# logic_vB.net
KiCad netlist of a schematic drawn in EAGLE
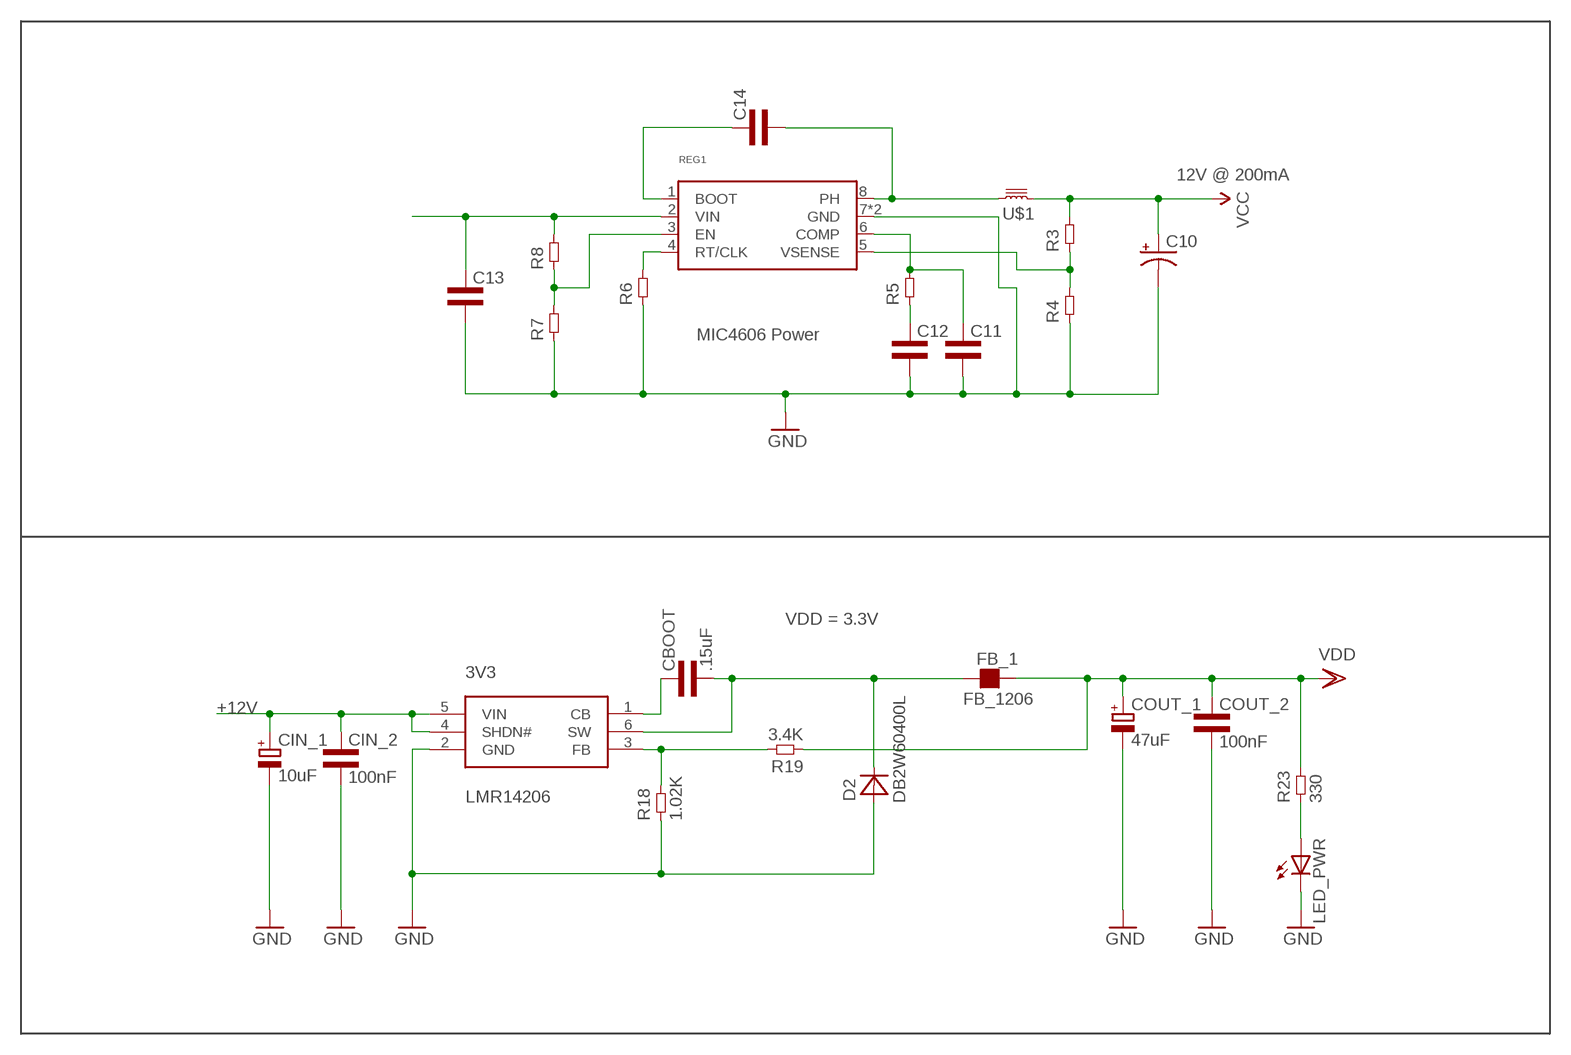
[diagram p0: schematic, sheet 1]
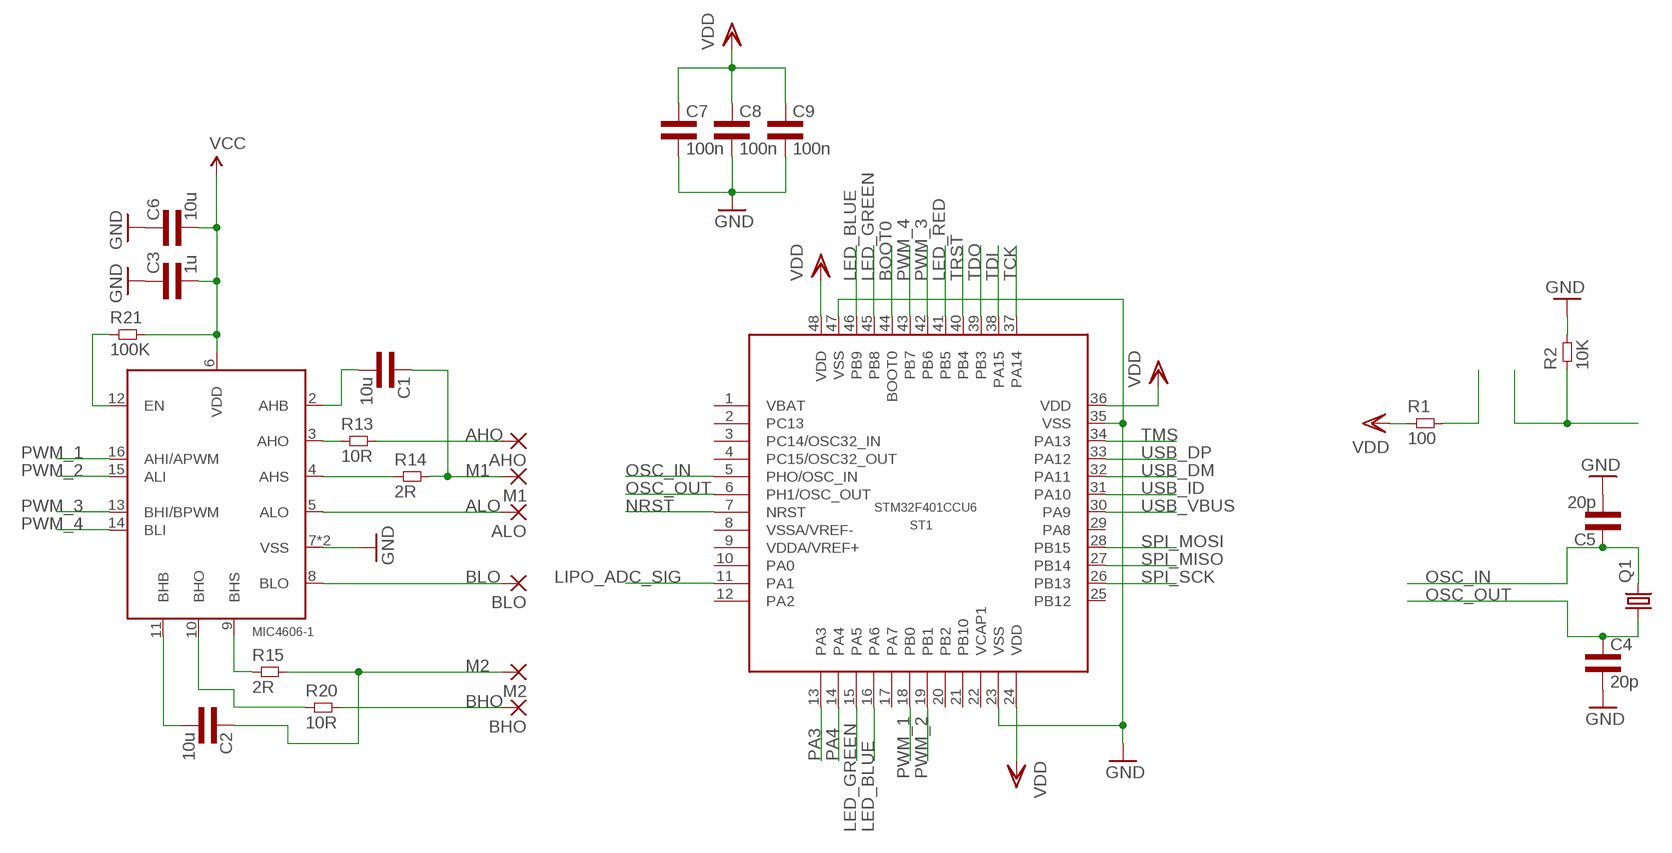
[diagram p1: schematic, sheet 2]
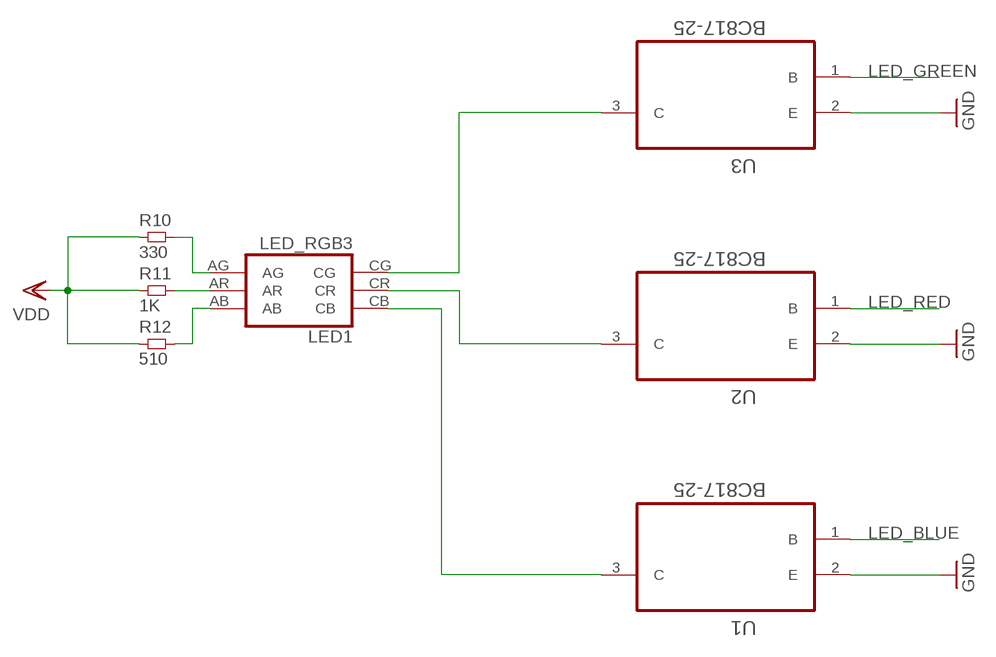
[diagram p2: schematic, sheet 3]
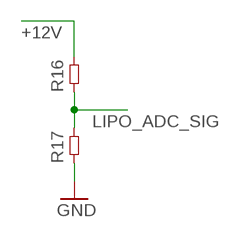
[diagram p3: schematic, sheet 4]

(export (version "E")
  (design (tool "Eeschema 10.0.6"))
  (components
    (comp (ref "R16")
      (value "RES0805L3")
      (footprint "eagle-import:0805L3")
      (libsource (lib "eagle-import") (part "RES0805L3"))
    )
    (comp (ref "R17")
      (value "RES0805L3")
      (footprint "eagle-import:0805L3")
      (libsource (lib "eagle-import") (part "RES0805L3"))
    )
    (comp (ref "AHO")
      (value "2,54/1,1")
      (footprint "eagle-import:2,54_1,1")
      (libsource (lib "eagle-import") (part "2,54/1,1"))
    )
    (comp (ref "ALO")
      (value "2,54/1,1")
      (footprint "eagle-import:2,54_1,1")
      (libsource (lib "eagle-import") (part "2,54/1,1"))
    )
    (comp (ref "BHO")
      (value "2,54/1,1")
      (footprint "eagle-import:2,54_1,1")
      (libsource (lib "eagle-import") (part "2,54/1,1"))
    )
    (comp (ref "BLO")
      (value "2,54/1,1")
      (footprint "eagle-import:2,54_1,1")
      (libsource (lib "eagle-import") (part "2,54/1,1"))
    )
    (comp (ref "C1")
      (value "10u")
      (footprint "eagle-import:0805L3")
      (libsource (lib "eagle-import") (part "CAP0805L3"))
    )
    (comp (ref "C2")
      (value "10u")
      (footprint "eagle-import:0805L3")
      (libsource (lib "eagle-import") (part "CAP0805L3"))
    )
    (comp (ref "C3")
      (value "1u")
      (footprint "eagle-import:0603L3")
      (libsource (lib "eagle-import") (part "CAP0603L3"))
    )
    (comp (ref "C4")
      (value "20p")
      (footprint "eagle-import:0402L3")
      (libsource (lib "eagle-import") (part "CAP0402L3"))
    )
    (comp (ref "C5")
      (value "20p")
      (footprint "eagle-import:0402L3")
      (libsource (lib "eagle-import") (part "CAP0402L3"))
    )
    (comp (ref "C6")
      (value "10u")
      (footprint "eagle-import:0603L3")
      (libsource (lib "eagle-import") (part "CAP0603L3"))
    )
    (comp (ref "C7")
      (value "100n")
      (footprint "eagle-import:0402L3")
      (libsource (lib "eagle-import") (part "CAP0402L3"))
    )
    (comp (ref "C8")
      (value "100n")
      (footprint "eagle-import:0402L3")
      (libsource (lib "eagle-import") (part "CAP0402L3"))
    )
    (comp (ref "C9")
      (value "100n")
      (footprint "eagle-import:0402L3")
      (libsource (lib "eagle-import") (part "CAP0402L3"))
    )
    (comp (ref "M1")
      (value "2,54/1,1")
      (footprint "eagle-import:2,54_1,1")
      (libsource (lib "eagle-import") (part "2,54/1,1"))
    )
    (comp (ref "M2")
      (value "2,54/1,1")
      (footprint "eagle-import:2,54_1,1")
      (libsource (lib "eagle-import") (part "2,54/1,1"))
    )
    (comp (ref "MD1")
      (value "MIC4606-1")
      (footprint "eagle-import:QFN44-16LD-PL-2")
      (libsource (lib "eagle-import") (part "MIC4606-1"))
    )
    (comp (ref "Q1")
      (value "CRYSTALCTS406")
      (footprint "eagle-import:CTS406")
      (libsource (lib "eagle-import") (part "CRYSTALCTS406"))
    )
    (comp (ref "R1")
      (value "100")
      (footprint "eagle-import:0402L3")
      (libsource (lib "eagle-import") (part "RES0402L3"))
    )
    (comp (ref "R2")
      (value "10K")
      (footprint "eagle-import:0402L3")
      (libsource (lib "eagle-import") (part "RES0402L3"))
    )
    (comp (ref "R13")
      (value "10R")
      (footprint "eagle-import:0805L3")
      (libsource (lib "eagle-import") (part "RES0805L3"))
    )
    (comp (ref "R14")
      (value "2R")
      (footprint "eagle-import:0805L3")
      (libsource (lib "eagle-import") (part "RES0805L3"))
    )
    (comp (ref "R15")
      (value "2R")
      (footprint "eagle-import:0805L3")
      (libsource (lib "eagle-import") (part "RES0805L3"))
    )
    (comp (ref "R20")
      (value "10R")
      (footprint "eagle-import:0805L3")
      (libsource (lib "eagle-import") (part "RES0805L3"))
    )
    (comp (ref "R21")
      (value "100K")
      (footprint "eagle-import:0603L3")
      (libsource (lib "eagle-import") (part "RES0603L3"))
    )
    (comp (ref "ST1")
      (value "STM32F401CCU6")
      (footprint "eagle-import:UFQFPN48")
      (libsource (lib "eagle-import") (part "STM32F401CCU6"))
    )
    (comp (ref "3V3")
      (value "LMR14206")
      (footprint "eagle-import:R-PDSO-G6")
      (libsource (lib "eagle-import") (part "LMR14206"))
    )
    (comp (ref "C10")
      (value "CPOL-US153CLV-0605")
      (footprint "eagle-import:153CLV-0605")
      (libsource (lib "eagle-import") (part "CPOL-US153CLV-0605"))
    )
    (comp (ref "C11")
      (value "CAP0603L3")
      (footprint "eagle-import:0603L3")
      (libsource (lib "eagle-import") (part "CAP0603L3"))
    )
    (comp (ref "C12")
      (value "CAP0603L3")
      (footprint "eagle-import:0603L3")
      (libsource (lib "eagle-import") (part "CAP0603L3"))
    )
    (comp (ref "C13")
      (value "CAP0805L3")
      (footprint "eagle-import:0805L3")
      (libsource (lib "eagle-import") (part "CAP0805L3"))
    )
    (comp (ref "C14")
      (value "CAP0603L3")
      (footprint "eagle-import:0603L3")
      (libsource (lib "eagle-import") (part "CAP0603L3"))
    )
    (comp (ref "CBOOT")
      (value ".15uF")
      (footprint "eagle-import:0603L3")
      (libsource (lib "eagle-import") (part "CAP0603L3"))
    )
    (comp (ref "CIN_1")
      (value "10uF")
      (footprint "eagle-import:B_3528-21W")
      (libsource (lib "eagle-import") (part "CPOL-EUB/3528-21W"))
    )
    (comp (ref "CIN_2")
      (value "100nF")
      (footprint "eagle-import:0603L3")
      (libsource (lib "eagle-import") (part "CAP0603L3"))
    )
    (comp (ref "COUT_1")
      (value "47uF")
      (footprint "eagle-import:B_3528-21W")
      (libsource (lib "eagle-import") (part "CPOL-EUB/3528-21W"))
    )
    (comp (ref "COUT_2")
      (value "100nF")
      (footprint "eagle-import:0603L3")
      (libsource (lib "eagle-import") (part "CAP0603L3"))
    )
    (comp (ref "D2")
      (value "DB2W60400L")
      (footprint "eagle-import:SC-109B")
      (libsource (lib "eagle-import") (part "DB2W60400L"))
    )
    (comp (ref "FB_1")
      (value "FB_1206")
      (footprint "eagle-import:L1206")
      (libsource (lib "eagle-import") (part "FB_1206"))
    )
    (comp (ref "LED_PWR")
      (value "LEDCHIP-LED0603")
      (footprint "eagle-import:CHIP-LED0603")
      (libsource (lib "eagle-import") (part "LEDCHIP-LED0603"))
    )
    (comp (ref "R3")
      (value "RES0603L3")
      (footprint "eagle-import:0603L3")
      (libsource (lib "eagle-import") (part "RES0603L3"))
    )
    (comp (ref "R4")
      (value "RES0603L3")
      (footprint "eagle-import:0603L3")
      (libsource (lib "eagle-import") (part "RES0603L3"))
    )
    (comp (ref "R5")
      (value "RES0603L3")
      (footprint "eagle-import:0603L3")
      (libsource (lib "eagle-import") (part "RES0603L3"))
    )
    (comp (ref "R6")
      (value "RES0603L3")
      (footprint "eagle-import:0603L3")
      (libsource (lib "eagle-import") (part "RES0603L3"))
    )
    (comp (ref "R7")
      (value "RES0603L3")
      (footprint "eagle-import:0603L3")
      (libsource (lib "eagle-import") (part "RES0603L3"))
    )
    (comp (ref "R8")
      (value "RES0603L3")
      (footprint "eagle-import:0603L3")
      (libsource (lib "eagle-import") (part "RES0603L3"))
    )
    (comp (ref "R18")
      (value "1.02K")
      (footprint "eagle-import:0402L3")
      (libsource (lib "eagle-import") (part "RES0402L3"))
    )
    (comp (ref "R19")
      (value "3.4K")
      (footprint "eagle-import:0402L3")
      (libsource (lib "eagle-import") (part "RES0402L3"))
    )
    (comp (ref "R23")
      (value "330")
      (footprint "eagle-import:0402L3")
      (libsource (lib "eagle-import") (part "RES0402L3"))
    )
    (comp (ref "REG1")
      (value "TPS54061")
      (footprint "eagle-import:S-PVSON-N8")
      (libsource (lib "eagle-import") (part "TPS54061"))
    )
    (comp (ref "U$1")
      (value "SDR0604")
      (footprint "eagle-import:SDR0604")
      (libsource (lib "eagle-import") (part "SDR0604"))
    )
    (comp (ref "LED1")
      (value "LED_RGB3")
      (footprint "eagle-import:RGBLED")
      (libsource (lib "eagle-import") (part "LED_RGB3"))
    )
    (comp (ref "R10")
      (value "330")
      (footprint "eagle-import:0402L3")
      (libsource (lib "eagle-import") (part "RES0402L3"))
    )
    (comp (ref "R11")
      (value "1K")
      (footprint "eagle-import:0402L3")
      (libsource (lib "eagle-import") (part "RES0402L3"))
    )
    (comp (ref "R12")
      (value "510")
      (footprint "eagle-import:0402L3")
      (libsource (lib "eagle-import") (part "RES0402L3"))
    )
    (comp (ref "U1")
      (value "BC817-25")
      (footprint "eagle-import:SOT95P240X97-3N")
      (libsource (lib "eagle-import") (part "BC817-25"))
    )
    (comp (ref "U2")
      (value "BC817-25")
      (footprint "eagle-import:SOT95P240X97-3N")
      (libsource (lib "eagle-import") (part "BC817-25"))
    )
    (comp (ref "U3")
      (value "BC817-25")
      (footprint "eagle-import:SOT95P240X97-3N")
      (libsource (lib "eagle-import") (part "BC817-25"))
    )
  )
  (nets
    (net (code "1") (name "+12V") (class "Default")
      (node (ref "3V3") (pin "4") (pinfunction "SHDN#_4") (pintype "bidirectional"))
      (node (ref "3V3") (pin "5") (pinfunction "VIN_5") (pintype "bidirectional"))
      (node (ref "C13") (pin "1") (pinfunction "1_1") (pintype "bidirectional"))
      (node (ref "CIN_1") (pin "+") (pinfunction "+_+") (pintype "passive"))
      (node (ref "CIN_2") (pin "P$1") (pinfunction "1_P$1") (pintype "bidirectional"))
      (node (ref "R16") (pin "2") (pinfunction "2_2") (pintype "bidirectional"))
      (node (ref "R8") (pin "P$2") (pinfunction "2_P$2") (pintype "bidirectional"))
      (node (ref "REG1") (pin "2") (pinfunction "VIN_2") (pintype "bidirectional"))
    )
    (net (code "2") (name "AHO") (class "Default")
      (node (ref "AHO") (pin "1") (pinfunction "P_1") (pintype "passive"))
      (node (ref "R13") (pin "2") (pinfunction "2_2") (pintype "bidirectional"))
    )
    (net (code "3") (name "ALO") (class "Default")
      (node (ref "ALO") (pin "1") (pinfunction "P_1") (pintype "passive"))
      (node (ref "MD1") (pin "5") (pinfunction "ALO_5") (pintype "bidirectional"))
    )
    (net (code "4") (name "BHO") (class "Default")
      (node (ref "BHO") (pin "1") (pinfunction "P_1") (pintype "passive"))
      (node (ref "R20") (pin "2") (pinfunction "2_2") (pintype "bidirectional"))
    )
    (net (code "5") (name "BLO") (class "Default")
      (node (ref "BLO") (pin "1") (pinfunction "P_1") (pintype "passive"))
      (node (ref "MD1") (pin "8") (pinfunction "BLO_8") (pintype "bidirectional"))
    )
    (net (code "6") (name "BOOT0") (class "Default")
      (node (ref "ST1") (pin "44") (pinfunction "BOOT0_44") (pintype "bidirectional"))
    )
    (net (code "7") (name "GND") (class "Default")
      (node (ref "3V3") (pin "2") (pinfunction "GND_2") (pintype "bidirectional"))
      (node (ref "C10") (pin "-") (pinfunction "-_-") (pintype "passive"))
      (node (ref "C11") (pin "P$2") (pinfunction "2_P$2") (pintype "bidirectional"))
      (node (ref "C12") (pin "P$2") (pinfunction "2_P$2") (pintype "bidirectional"))
      (node (ref "C13") (pin "2") (pinfunction "2_2") (pintype "bidirectional"))
      (node (ref "C3") (pin "P$1") (pinfunction "1_P$1") (pintype "bidirectional"))
      (node (ref "C4") (pin "P$2") (pinfunction "2_P$2") (pintype "bidirectional"))
      (node (ref "C5") (pin "P$2") (pinfunction "2_P$2") (pintype "bidirectional"))
      (node (ref "C6") (pin "P$1") (pinfunction "1_P$1") (pintype "bidirectional"))
      (node (ref "C7") (pin "P$2") (pinfunction "2_P$2") (pintype "bidirectional"))
      (node (ref "C8") (pin "P$2") (pinfunction "2_P$2") (pintype "bidirectional"))
      (node (ref "C9") (pin "P$2") (pinfunction "2_P$2") (pintype "bidirectional"))
      (node (ref "CIN_1") (pin "-") (pinfunction "-_-") (pintype "passive"))
      (node (ref "CIN_2") (pin "P$2") (pinfunction "2_P$2") (pintype "bidirectional"))
      (node (ref "COUT_1") (pin "-") (pinfunction "-_-") (pintype "passive"))
      (node (ref "COUT_2") (pin "P$2") (pinfunction "2_P$2") (pintype "bidirectional"))
      (node (ref "D2") (pin "2") (pinfunction "A_2") (pintype "passive"))
      (node (ref "LED_PWR") (pin "C") (pinfunction "C_C") (pintype "passive"))
      (node (ref "MD1") (pin "7") (pinfunction "VSS_7") (pintype "bidirectional"))
      (node (ref "MD1") (pin "TP") (pinfunction "VSS_TP") (pintype "bidirectional"))
      (node (ref "R17") (pin "1") (pinfunction "1_1") (pintype "bidirectional"))
      (node (ref "R18") (pin "P$1") (pinfunction "1_P$1") (pintype "bidirectional"))
      (node (ref "R2") (pin "P$2") (pinfunction "2_P$2") (pintype "bidirectional"))
      (node (ref "R4") (pin "P$1") (pinfunction "1_P$1") (pintype "bidirectional"))
      (node (ref "R6") (pin "P$1") (pinfunction "1_P$1") (pintype "bidirectional"))
      (node (ref "R7") (pin "P$1") (pinfunction "1_P$1") (pintype "bidirectional"))
      (node (ref "REG1") (pin "7") (pinfunction "GND_7") (pintype "bidirectional"))
      (node (ref "REG1") (pin "P$1") (pinfunction "GND_P$1") (pintype "bidirectional"))
      (node (ref "ST1") (pin "23") (pinfunction "VSS_23") (pintype "bidirectional"))
      (node (ref "ST1") (pin "35") (pinfunction "VSS_35") (pintype "bidirectional"))
      (node (ref "ST1") (pin "47") (pinfunction "VSS_47") (pintype "bidirectional"))
      (node (ref "U1") (pin "2") (pinfunction "E_2") (pintype "passive"))
      (node (ref "U2") (pin "2") (pinfunction "E_2") (pintype "passive"))
      (node (ref "U3") (pin "2") (pinfunction "E_2") (pintype "passive"))
    )
    (net (code "8") (name "LED_BLUE") (class "Default")
      (node (ref "ST1") (pin "16") (pinfunction "PA6_16") (pintype "bidirectional"))
      (node (ref "ST1") (pin "46") (pinfunction "PB9_46") (pintype "bidirectional"))
      (node (ref "U1") (pin "1") (pinfunction "B_1") (pintype "passive"))
    )
    (net (code "9") (name "LED_GREEN") (class "Default")
      (node (ref "ST1") (pin "15") (pinfunction "PA5_15") (pintype "bidirectional"))
      (node (ref "ST1") (pin "45") (pinfunction "PB8_45") (pintype "bidirectional"))
      (node (ref "U3") (pin "1") (pinfunction "B_1") (pintype "passive"))
    )
    (net (code "10") (name "LED_RED") (class "Default")
      (node (ref "ST1") (pin "41") (pinfunction "PB5_41") (pintype "bidirectional"))
      (node (ref "U2") (pin "1") (pinfunction "B_1") (pintype "passive"))
    )
    (net (code "11") (name "LIPO_ADC_SIG") (class "Default")
      (node (ref "R16") (pin "1") (pinfunction "1_1") (pintype "bidirectional"))
      (node (ref "R17") (pin "2") (pinfunction "2_2") (pintype "bidirectional"))
      (node (ref "ST1") (pin "11") (pinfunction "PA1_11") (pintype "bidirectional"))
    )
    (net (code "12") (name "M1") (class "Default")
      (node (ref "C1") (pin "1") (pinfunction "1_1") (pintype "bidirectional"))
      (node (ref "M1") (pin "1") (pinfunction "P_1") (pintype "passive"))
      (node (ref "R14") (pin "2") (pinfunction "2_2") (pintype "bidirectional"))
    )
    (net (code "13") (name "M2") (class "Default")
      (node (ref "C2") (pin "1") (pinfunction "1_1") (pintype "bidirectional"))
      (node (ref "M2") (pin "1") (pinfunction "P_1") (pintype "passive"))
      (node (ref "R15") (pin "2") (pinfunction "2_2") (pintype "bidirectional"))
    )
    (net (code "14") (name "NRST") (class "Default")
      (node (ref "ST1") (pin "7") (pinfunction "NRST_7") (pintype "bidirectional"))
    )
    (net (code "15") (name "Net-(3V3-CB)") (class "Default")
      (node (ref "3V3") (pin "1") (pinfunction "CB_1") (pintype "bidirectional"))
      (node (ref "CBOOT") (pin "P$1") (pinfunction "1_P$1") (pintype "bidirectional"))
    )
    (net (code "16") (name "Net-(3V3-FB)") (class "Default")
      (node (ref "3V3") (pin "3") (pinfunction "FB_3") (pintype "bidirectional"))
      (node (ref "R18") (pin "P$2") (pinfunction "2_P$2") (pintype "bidirectional"))
      (node (ref "R19") (pin "P$2") (pinfunction "2_P$2") (pintype "bidirectional"))
    )
    (net (code "17") (name "Net-(3V3-SW)") (class "Default")
      (node (ref "3V3") (pin "6") (pinfunction "SW_6") (pintype "bidirectional"))
      (node (ref "CBOOT") (pin "P$2") (pinfunction "2_P$2") (pintype "bidirectional"))
      (node (ref "D2") (pin "1") (pinfunction "C_1") (pintype "passive"))
      (node (ref "FB_1") (pin "1") (pinfunction "1_1") (pintype "passive"))
    )
    (net (code "18") (name "Net-(C11-1)") (class "Default")
      (node (ref "C11") (pin "P$1") (pinfunction "1_P$1") (pintype "bidirectional"))
      (node (ref "R5") (pin "P$2") (pinfunction "2_P$2") (pintype "bidirectional"))
      (node (ref "REG1") (pin "6") (pinfunction "COMP_6") (pintype "bidirectional"))
    )
    (net (code "19") (name "Net-(C12-1)") (class "Default")
      (node (ref "C12") (pin "P$1") (pinfunction "1_P$1") (pintype "bidirectional"))
      (node (ref "R5") (pin "P$1") (pinfunction "1_P$1") (pintype "bidirectional"))
    )
    (net (code "20") (name "Net-(C14-1)") (class "Default")
      (node (ref "C14") (pin "P$1") (pinfunction "1_P$1") (pintype "bidirectional"))
      (node (ref "REG1") (pin "1") (pinfunction "BOOT_1") (pintype "bidirectional"))
    )
    (net (code "21") (name "Net-(C14-2)") (class "Default")
      (node (ref "C14") (pin "P$2") (pinfunction "2_P$2") (pintype "bidirectional"))
      (node (ref "REG1") (pin "8") (pinfunction "PH_8") (pintype "bidirectional"))
      (node (ref "U$1") (pin "2") (pinfunction "2_2") (pintype "bidirectional"))
    )
    (net (code "22") (name "Net-(MD1-AHB)") (class "Default")
      (node (ref "C1") (pin "2") (pinfunction "2_2") (pintype "bidirectional"))
      (node (ref "MD1") (pin "2") (pinfunction "AHB_2") (pintype "bidirectional"))
    )
    (net (code "23") (name "Net-(MD1-AHO)") (class "Default")
      (node (ref "MD1") (pin "3") (pinfunction "AHO_3") (pintype "bidirectional"))
      (node (ref "R13") (pin "1") (pinfunction "1_1") (pintype "bidirectional"))
    )
    (net (code "24") (name "Net-(MD1-AHS)") (class "Default")
      (node (ref "MD1") (pin "4") (pinfunction "AHS_4") (pintype "bidirectional"))
      (node (ref "R14") (pin "1") (pinfunction "1_1") (pintype "bidirectional"))
    )
    (net (code "25") (name "Net-(MD1-BHB)") (class "Default")
      (node (ref "C2") (pin "2") (pinfunction "2_2") (pintype "bidirectional"))
      (node (ref "MD1") (pin "11") (pinfunction "BHB_11") (pintype "bidirectional"))
    )
    (net (code "26") (name "Net-(MD1-BHO)") (class "Default")
      (node (ref "MD1") (pin "10") (pinfunction "BHO_10") (pintype "bidirectional"))
      (node (ref "R20") (pin "1") (pinfunction "1_1") (pintype "bidirectional"))
    )
    (net (code "27") (name "Net-(MD1-BHS)") (class "Default")
      (node (ref "MD1") (pin "9") (pinfunction "BHS_9") (pintype "bidirectional"))
      (node (ref "R15") (pin "1") (pinfunction "1_1") (pintype "bidirectional"))
    )
    (net (code "28") (name "Net-(MD1-EN)") (class "Default")
      (node (ref "MD1") (pin "12") (pinfunction "EN_12") (pintype "bidirectional"))
      (node (ref "R21") (pin "P$1") (pinfunction "1_P$1") (pintype "bidirectional"))
    )
    (net (code "29") (name "Net-(R3-1)") (class "Default")
      (node (ref "R3") (pin "P$1") (pinfunction "1_P$1") (pintype "bidirectional"))
      (node (ref "R4") (pin "P$2") (pinfunction "2_P$2") (pintype "bidirectional"))
      (node (ref "REG1") (pin "5") (pinfunction "VSENSE_5") (pintype "bidirectional"))
    )
    (net (code "30") (name "Net-(R6-2)") (class "Default")
      (node (ref "R6") (pin "P$2") (pinfunction "2_P$2") (pintype "bidirectional"))
      (node (ref "REG1") (pin "4") (pinfunction "RT/CLK_4") (pintype "bidirectional"))
    )
    (net (code "31") (name "Net-(R7-2)") (class "Default")
      (node (ref "R7") (pin "P$2") (pinfunction "2_P$2") (pintype "bidirectional"))
      (node (ref "R8") (pin "P$1") (pinfunction "1_P$1") (pintype "bidirectional"))
      (node (ref "REG1") (pin "3") (pinfunction "EN_3") (pintype "bidirectional"))
    )
    (net (code "32") (name "Net-(R10-2)") (class "Default")
      (node (ref "LED1") (pin "AG") (pinfunction "AG_AG") (pintype "bidirectional"))
      (node (ref "R10") (pin "P$2") (pinfunction "2_P$2") (pintype "bidirectional"))
    )
    (net (code "33") (name "Net-(R11-2)") (class "Default")
      (node (ref "LED1") (pin "AR") (pinfunction "AR_AR") (pintype "bidirectional"))
      (node (ref "R11") (pin "P$2") (pinfunction "2_P$2") (pintype "bidirectional"))
    )
    (net (code "34") (name "Net-(R12-2)") (class "Default")
      (node (ref "LED1") (pin "AB") (pinfunction "AB_AB") (pintype "bidirectional"))
      (node (ref "R12") (pin "P$2") (pinfunction "2_P$2") (pintype "bidirectional"))
    )
    (net (code "35") (name "Net-(R23-1)") (class "Default")
      (node (ref "LED_PWR") (pin "A") (pinfunction "A_A") (pintype "passive"))
      (node (ref "R23") (pin "P$1") (pinfunction "1_P$1") (pintype "bidirectional"))
    )
    (net (code "36") (name "Net-(U1-C)") (class "Default")
      (node (ref "LED1") (pin "CB") (pinfunction "CB_CB") (pintype "bidirectional"))
      (node (ref "U1") (pin "3") (pinfunction "C_3") (pintype "passive"))
    )
    (net (code "37") (name "Net-(U2-C)") (class "Default")
      (node (ref "LED1") (pin "CR") (pinfunction "CR_CR") (pintype "bidirectional"))
      (node (ref "U2") (pin "3") (pinfunction "C_3") (pintype "passive"))
    )
    (net (code "38") (name "Net-(U3-C)") (class "Default")
      (node (ref "LED1") (pin "CG") (pinfunction "CG_CG") (pintype "bidirectional"))
      (node (ref "U3") (pin "3") (pinfunction "C_3") (pintype "passive"))
    )
    (net (code "39") (name "OSC_IN") (class "Default")
      (node (ref "C5") (pin "P$1") (pinfunction "1_P$1") (pintype "bidirectional"))
      (node (ref "Q1") (pin "3") (pinfunction "2_3") (pintype "passive"))
      (node (ref "ST1") (pin "5") (pinfunction "PHO/OSC_IN_5") (pintype "bidirectional"))
    )
    (net (code "40") (name "OSC_OUT") (class "Default")
      (node (ref "C4") (pin "P$1") (pinfunction "1_P$1") (pintype "bidirectional"))
      (node (ref "Q1") (pin "1") (pinfunction "1_1") (pintype "passive"))
      (node (ref "ST1") (pin "6") (pinfunction "PH1/OSC_OUT_6") (pintype "bidirectional"))
    )
    (net (code "41") (name "PA3") (class "Default")
      (node (ref "ST1") (pin "13") (pinfunction "PA3_13") (pintype "bidirectional"))
    )
    (net (code "42") (name "PA4") (class "Default")
      (node (ref "ST1") (pin "14") (pinfunction "PA4_14") (pintype "bidirectional"))
    )
    (net (code "43") (name "PWM_1") (class "Default")
      (node (ref "MD1") (pin "16") (pinfunction "AHI/APWM_16") (pintype "bidirectional"))
      (node (ref "ST1") (pin "18") (pinfunction "PB0_18") (pintype "bidirectional"))
    )
    (net (code "44") (name "PWM_2") (class "Default")
      (node (ref "MD1") (pin "15") (pinfunction "ALI_15") (pintype "bidirectional"))
      (node (ref "ST1") (pin "19") (pinfunction "PB1_19") (pintype "bidirectional"))
    )
    (net (code "45") (name "PWM_3") (class "Default")
      (node (ref "MD1") (pin "13") (pinfunction "BHI/BPWM_13") (pintype "bidirectional"))
      (node (ref "ST1") (pin "42") (pinfunction "PB6_42") (pintype "bidirectional"))
    )
    (net (code "46") (name "PWM_4") (class "Default")
      (node (ref "MD1") (pin "14") (pinfunction "BLI_14") (pintype "bidirectional"))
      (node (ref "ST1") (pin "43") (pinfunction "PB7_43") (pintype "bidirectional"))
    )
    (net (code "47") (name "SPI_MISO") (class "Default")
      (node (ref "ST1") (pin "27") (pinfunction "PB14_27") (pintype "bidirectional"))
    )
    (net (code "48") (name "SPI_MOSI") (class "Default")
      (node (ref "ST1") (pin "28") (pinfunction "PB15_28") (pintype "bidirectional"))
    )
    (net (code "49") (name "SPI_SCK") (class "Default")
      (node (ref "ST1") (pin "26") (pinfunction "PB13_26") (pintype "bidirectional"))
    )
    (net (code "50") (name "TCK") (class "Default")
      (node (ref "ST1") (pin "37") (pinfunction "PA14_37") (pintype "bidirectional"))
    )
    (net (code "51") (name "TDI") (class "Default")
      (node (ref "ST1") (pin "38") (pinfunction "PA15_38") (pintype "bidirectional"))
    )
    (net (code "52") (name "TDO") (class "Default")
      (node (ref "ST1") (pin "39") (pinfunction "PB3_39") (pintype "bidirectional"))
    )
    (net (code "53") (name "TMS") (class "Default")
      (node (ref "ST1") (pin "34") (pinfunction "PA13_34") (pintype "bidirectional"))
    )
    (net (code "54") (name "TRST") (class "Default")
      (node (ref "ST1") (pin "40") (pinfunction "PB4_40") (pintype "bidirectional"))
    )
    (net (code "55") (name "USB_DM") (class "Default")
      (node (ref "ST1") (pin "32") (pinfunction "PA11_32") (pintype "bidirectional"))
    )
    (net (code "56") (name "USB_DP") (class "Default")
      (node (ref "ST1") (pin "33") (pinfunction "PA12_33") (pintype "bidirectional"))
    )
    (net (code "57") (name "USB_ID") (class "Default")
      (node (ref "ST1") (pin "31") (pinfunction "PA10_31") (pintype "bidirectional"))
    )
    (net (code "58") (name "USB_VBUS") (class "Default")
      (node (ref "ST1") (pin "30") (pinfunction "PA9_30") (pintype "bidirectional"))
    )
    (net (code "59") (name "VCC") (class "Default")
      (node (ref "C10") (pin "+") (pinfunction "+_+") (pintype "passive"))
      (node (ref "C3") (pin "P$2") (pinfunction "2_P$2") (pintype "bidirectional"))
      (node (ref "C6") (pin "P$2") (pinfunction "2_P$2") (pintype "bidirectional"))
      (node (ref "MD1") (pin "6") (pinfunction "VDD_6") (pintype "bidirectional"))
      (node (ref "R21") (pin "P$2") (pinfunction "2_P$2") (pintype "bidirectional"))
      (node (ref "R3") (pin "P$2") (pinfunction "2_P$2") (pintype "bidirectional"))
      (node (ref "U$1") (pin "1") (pinfunction "1_1") (pintype "bidirectional"))
    )
    (net (code "60") (name "VDD") (class "Default")
      (node (ref "C7") (pin "P$1") (pinfunction "1_P$1") (pintype "bidirectional"))
      (node (ref "C8") (pin "P$1") (pinfunction "1_P$1") (pintype "bidirectional"))
      (node (ref "C9") (pin "P$1") (pinfunction "1_P$1") (pintype "bidirectional"))
      (node (ref "COUT_1") (pin "+") (pinfunction "+_+") (pintype "passive"))
      (node (ref "COUT_2") (pin "P$1") (pinfunction "1_P$1") (pintype "bidirectional"))
      (node (ref "FB_1") (pin "2") (pinfunction "2_2") (pintype "passive"))
      (node (ref "R1") (pin "P$1") (pinfunction "1_P$1") (pintype "bidirectional"))
      (node (ref "R10") (pin "P$1") (pinfunction "1_P$1") (pintype "bidirectional"))
      (node (ref "R11") (pin "P$1") (pinfunction "1_P$1") (pintype "bidirectional"))
      (node (ref "R12") (pin "P$1") (pinfunction "1_P$1") (pintype "bidirectional"))
      (node (ref "R19") (pin "P$1") (pinfunction "1_P$1") (pintype "bidirectional"))
      (node (ref "R23") (pin "P$2") (pinfunction "2_P$2") (pintype "bidirectional"))
      (node (ref "ST1") (pin "24") (pinfunction "VDD_24") (pintype "bidirectional"))
      (node (ref "ST1") (pin "36") (pinfunction "VDD_36") (pintype "bidirectional"))
      (node (ref "ST1") (pin "48") (pinfunction "VDD_48") (pintype "bidirectional"))
    )
    (net (code "61") (name "unconnected-(R1-2-PadP$2)") (class "Default")
      (node (ref "R1") (pin "P$2") (pinfunction "2_P$2") (pintype "bidirectional"))
    )
    (net (code "62") (name "unconnected-(R2-1-PadP$1)") (class "Default")
      (node (ref "R2") (pin "P$1") (pinfunction "1_P$1") (pintype "bidirectional"))
    )
    (net (code "63") (name "unconnected-(ST1-PA0-Pad10)") (class "Default")
      (node (ref "ST1") (pin "10") (pinfunction "PA0_10") (pintype "bidirectional"))
    )
    (net (code "64") (name "unconnected-(ST1-PA2-Pad12)") (class "Default")
      (node (ref "ST1") (pin "12") (pinfunction "PA2_12") (pintype "bidirectional"))
    )
    (net (code "65") (name "unconnected-(ST1-PA7-Pad17)") (class "Default")
      (node (ref "ST1") (pin "17") (pinfunction "PA7_17") (pintype "bidirectional"))
    )
    (net (code "66") (name "unconnected-(ST1-PA8-Pad29)") (class "Default")
      (node (ref "ST1") (pin "29") (pinfunction "PA8_29") (pintype "bidirectional"))
    )
    (net (code "67") (name "unconnected-(ST1-PB2-Pad20)") (class "Default")
      (node (ref "ST1") (pin "20") (pinfunction "PB2_20") (pintype "bidirectional"))
    )
    (net (code "68") (name "unconnected-(ST1-PB10-Pad21)") (class "Default")
      (node (ref "ST1") (pin "21") (pinfunction "PB10_21") (pintype "bidirectional"))
    )
    (net (code "69") (name "unconnected-(ST1-PB12-Pad25)") (class "Default")
      (node (ref "ST1") (pin "25") (pinfunction "PB12_25") (pintype "bidirectional"))
    )
    (net (code "70") (name "unconnected-(ST1-PC13-Pad2)") (class "Default")
      (node (ref "ST1") (pin "2") (pinfunction "PC13_2") (pintype "bidirectional"))
    )
    (net (code "71") (name "unconnected-(ST1-PC14{slash}OSC32_IN-Pad3)") (class "Default")
      (node (ref "ST1") (pin "3") (pinfunction "PC14/OSC32_IN_3") (pintype "bidirectional"))
    )
    (net (code "72") (name "unconnected-(ST1-PC15{slash}OSC32_OUT-Pad4)") (class "Default")
      (node (ref "ST1") (pin "4") (pinfunction "PC15/OSC32_OUT_4") (pintype "bidirectional"))
    )
    (net (code "73") (name "unconnected-(ST1-VBAT-Pad1)") (class "Default")
      (node (ref "ST1") (pin "1") (pinfunction "VBAT_1") (pintype "bidirectional"))
    )
    (net (code "74") (name "unconnected-(ST1-VCAP1-Pad22)") (class "Default")
      (node (ref "ST1") (pin "22") (pinfunction "VCAP1_22") (pintype "bidirectional"))
    )
    (net (code "75") (name "unconnected-(ST1-VDDA{slash}VREF+-Pad9)") (class "Default")
      (node (ref "ST1") (pin "9") (pinfunction "VDDA/VREF+_9") (pintype "bidirectional"))
    )
    (net (code "76") (name "unconnected-(ST1-VSSA{slash}VREF--Pad8)") (class "Default")
      (node (ref "ST1") (pin "8") (pinfunction "VSSA/VREF-_8") (pintype "bidirectional"))
    )
  )
)
